# RF_Gen.net
KiCad netlist of a schematic drawn in Altium Designer
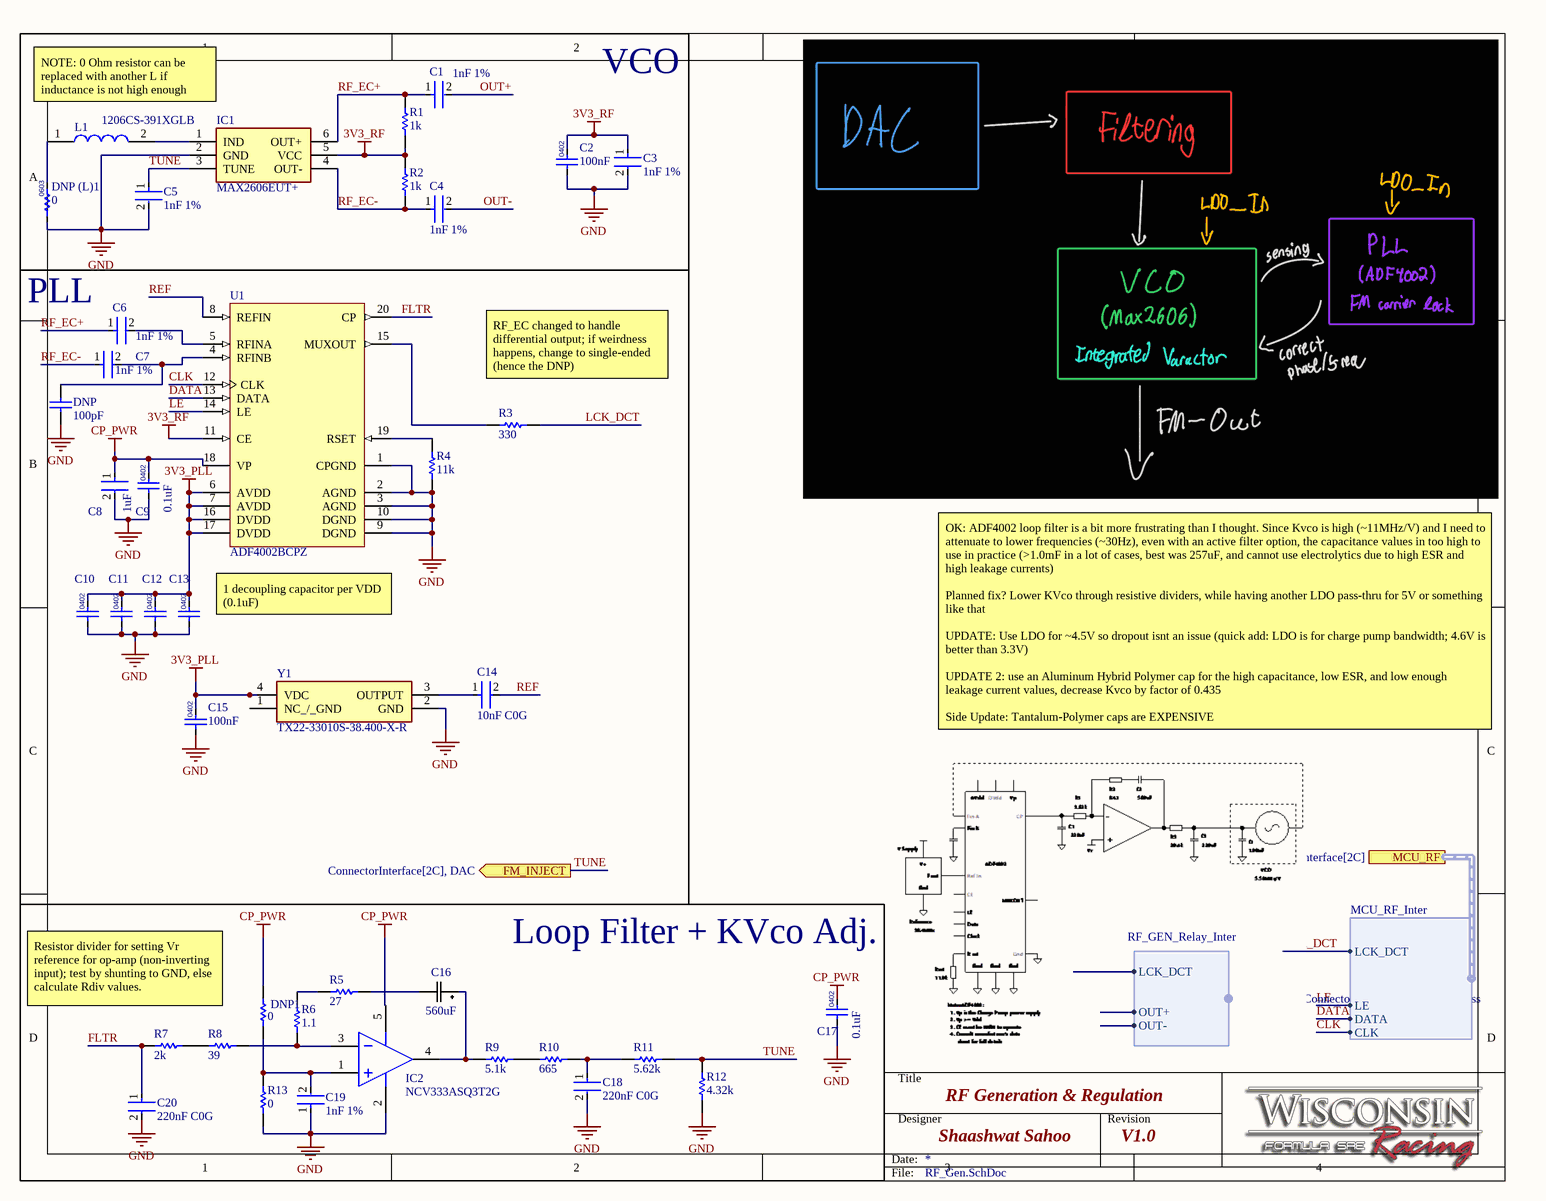
[diagram p0: RF_Gen.SchDoc]

(export (version "E")
  (design (tool "Eeschema 10.0.6"))
  (components
    (comp (ref "C1")
      (value "1nF 1%")
      (footprint "FP-GRT155-0_05-IPC_A")
      (description "Multi-Layer Ceramic Capacitor 1nF 50V C0G ±1% 0402 Paper T/R\r\n\r\nGRT1555C1H102FA02D")
      (libsource (lib "Altium Content Vault") (part "02cd4be3c70576c341d710602a673aa"))
    )
    (comp (ref "C2")
      (value "100nF")
      (footprint "FP-CC0402-IPC_B")
      (fields (field (name "TOLERANCE") "10%"))
      (libsource (lib "University of Wisconsin Formula FSAE") (part "0402 ceramic cap"))
    )
    (comp (ref "C3")
      (value "1nF 1%")
      (footprint "FP-GRT155-0_05-IPC_A")
      (description "Multi-Layer Ceramic Capacitor 1nF 50V C0G ±1% 0402 Paper T/R\r\n\r\nGRT1555C1H102FA02D")
      (libsource (lib "Altium Content Vault") (part "02cd4be3c70576c341d710602a673aa"))
    )
    (comp (ref "C4")
      (value "1nF 1%")
      (footprint "FP-GRT155-0_05-IPC_A")
      (description "Multi-Layer Ceramic Capacitor 1nF 50V C0G ±1% 0402 Paper T/R\r\n\r\nGRT1555C1H102FA02D")
      (libsource (lib "Altium Content Vault") (part "02cd4be3c70576c341d710602a673aa"))
    )
    (comp (ref "C5")
      (value "1nF 1%")
      (footprint "FP-GRT155-0_05-IPC_A")
      (description "Multi-Layer Ceramic Capacitor 1nF 50V C0G ±1% 0402 Paper T/R\r\n\r\nGRT1555C1H102FA02D")
      (libsource (lib "Altium Content Vault") (part "02cd4be3c70576c341d710602a673aa"))
    )
    (comp (ref "C6")
      (value "1nF 1%")
      (footprint "FP-GRT155-0_05-IPC_A")
      (description "Multi-Layer Ceramic Capacitor 1nF 50V C0G ±1% 0402 Paper T/R\r\n\r\nGRT1555C1H102FA02D")
      (libsource (lib "Altium Content Vault") (part "02cd4be3c70576c341d710602a673aa"))
    )
    (comp (ref "C7")
      (value "1nF 1%")
      (footprint "FP-GRT155-0_05-IPC_A")
      (description "Multi-Layer Ceramic Capacitor 1nF 50V C0G ±1% 0402 Paper T/R\r\n\r\nGRT1555C1H102FA02D")
      (libsource (lib "Altium Content Vault") (part "02cd4be3c70576c341d710602a673aa"))
    )
    (comp (ref "C8")
      (value "1uF")
      (footprint "FP-GRM155-0_1-IPC_A")
      (description "Chip Multilayer Ceramic Capacitors for General Purpose, 0402, 1.0uF, X7R, 15%, 10%, 10V")
      (libsource (lib "Altium Content Vault") (part "11868f565c42a9108669ba33697ecf6"))
    )
    (comp (ref "C9")
      (value "0.1uF")
      (footprint "FP-CC0402-IPC_B")
      (fields (field (name "TOLERANCE") "10%"))
      (libsource (lib "University of Wisconsin Formula FSAE") (part "0402 ceramic cap"))
    )
    (comp (ref "C10")
      (value "0.1uF")
      (footprint "FP-CC0402-IPC_B")
      (fields (field (name "TOLERANCE") "10%"))
      (libsource (lib "University of Wisconsin Formula FSAE") (part "0402 ceramic cap"))
    )
    (comp (ref "C11")
      (value "0.1uF")
      (footprint "FP-CC0402-IPC_B")
      (fields (field (name "TOLERANCE") "10%"))
      (libsource (lib "University of Wisconsin Formula FSAE") (part "0402 ceramic cap"))
    )
    (comp (ref "C12")
      (value "0.1uF")
      (footprint "FP-CC0402-IPC_B")
      (fields (field (name "TOLERANCE") "10%"))
      (libsource (lib "University of Wisconsin Formula FSAE") (part "0402 ceramic cap"))
    )
    (comp (ref "C13")
      (value "0.1uF")
      (footprint "FP-CC0402-IPC_B")
      (fields (field (name "TOLERANCE") "10%"))
      (libsource (lib "University of Wisconsin Formula FSAE") (part "0402 ceramic cap"))
    )
    (comp (ref "C14")
      (value "10nF C0G")
      (footprint "FP-GRM155-0_15-MFG")
      (description "Chip Multilayer Ceramic Capacitors for General Purpose, 0402, 10000pF, C0G, 30ppm/°C, 5%, 35V")
      (libsource (lib "Altium Content Vault") (part "b4654b650e69147ec39a6b967a45e02"))
    )
    (comp (ref "C15")
      (value "100nF")
      (footprint "FP-CC0402-IPC_B")
      (fields (field (name "TOLERANCE") "10%"))
      (libsource (lib "University of Wisconsin Formula FSAE") (part "0402 ceramic cap"))
    )
    (comp (ref "C16")
      (value "560uF")
      (footprint "CAP_GY_10X10_NCH")
      (description "Description")
      (fields
        (field (name "MANUFACTURER_PART_NUMBER") "GYB1J560MCQ1GS")
        (field (name "COPYRIGHT") "Copyright (C) 2025 Ultra Librarian. All rights reserved.")
      )
      (libsource (lib "University of Wisconsin Formula FSAE") (part "GYB1J560MCQ1GS"))
    )
    (comp (ref "C17")
      (value "0.1uF")
      (footprint "FP-CC0402-IPC_B")
      (fields (field (name "TOLERANCE") "10%"))
      (libsource (lib "University of Wisconsin Formula FSAE") (part "0402 ceramic cap"))
    )
    (comp (ref "C18")
      (value "220nF C0G")
      (footprint "FP-GRM31C-0_2-e0_3_0_8-IPC_B")
      (description "Chip Multilayer Ceramic Capacitors for General Purpose, 1206, 0.22uF, C0G, 30ppm/°C, 5%, 25V")
      (libsource (lib "Altium Content Vault") (part "02cd4be3c70576c341d710602a673aa"))
    )
    (comp (ref "C19")
      (value "1nF 1%")
      (footprint "FP-GRT155-0_05-IPC_A")
      (description "Multi-Layer Ceramic Capacitor 1nF 50V C0G ±1% 0402 Paper T/R\r\n\r\nGRT1555C1H102FA02D")
      (libsource (lib "Altium Content Vault") (part "02cd4be3c70576c341d710602a673aa"))
    )
    (comp (ref "C20")
      (value "220nF C0G")
      (footprint "FP-GRM31C-0_2-e0_3_0_8-IPC_B")
      (description "Chip Multilayer Ceramic Capacitors for General Purpose, 1206, 0.22uF, C0G, 30ppm/°C, 5%, 25V")
      (libsource (lib "Altium Content Vault") (part "02cd4be3c70576c341d710602a673aa"))
    )
    (comp (ref "DNP")
      (value "100pF")
      (footprint "CAPC1005X55X25ML05T10")
      (fields (field (name "MANUFACTURER") "Murata") (field (name "PART NUMBER") "GRM1555C1H101JA01D"))
      (libsource (lib "Altium Content Vault") (part "CAP"))
    )
    (comp (ref "DNP (L)1")
      (value "0")
      (footprint "Res0603-type-2")
      (description "Fixed Resistor, Metal Glaze/thick Film, 0.1W, 0ohm, Surface Mount, 0603")
      (fields (field (name "TOLERANCE") "0.1%") (field (name "POWER") "100mW"))
      (libsource (lib "University of Wisconsin Formula FSAE") (part "RES 0603"))
    )
    (comp (ref "DNP1")
      (value "0")
      (footprint "RESC1005X40X25NL05T10")
      (fields (field (name "MANUFACTURER") "Yageo / Phycomp") (field (name "PART NUMBER") "RC0402JR-070RL"))
      (libsource (lib "Altium Content Vault") (part "RES"))
    )
    (comp (ref "IC1")
      (value "MAX2606EUT+")
      (footprint "SamacSys:SOT95P280X145-6N")
      (description "Integrated Circuit")
      (fields (field (name "MOUSER PART NUMBER") "700-MAX2606EUT+"))
      (libsource (lib "*") (part "MAX2606EUT+"))
    )
    (comp (ref "IC2")
      (value "NCV333ASQ3T2G")
      (footprint "SOT65P210X110-5N")
      (description "Low Offset Voltage: 10 V max (NCS333)")
      (fields (field (name "MOUSER PART NUMBER") "863-NCV333ASQ3T2G"))
      (libsource (lib "University of Wisconsin Formula FSAE") (part "NCV333ASQ3T2G"))
    )
    (comp (ref "L1")
      (value "1206CS-391XGLB")
      (footprint "SamacSys:INDC3622X152N")
      (description "Inductor")
      (libsource (lib "*") (part "1206CS-391XGLB"))
    )
    (comp (ref "R1")
      (value "1k")
      (footprint "RESC1005X40X25LL05T10")
      (fields (field (name "PART NUMBER") "RC0402JR-071KL") (field (name "MANUFACTURER") "Yageo / Phycomp"))
      (libsource (lib "Altium Content Vault") (part "RES"))
    )
    (comp (ref "R2")
      (value "1k")
      (footprint "RESC1005X40X25LL05T10")
      (fields (field (name "PART NUMBER") "RC0402JR-071KL") (field (name "MANUFACTURER") "Yageo / Phycomp"))
      (libsource (lib "Altium Content Vault") (part "RES"))
    )
    (comp (ref "R3")
      (value "330")
      (footprint "RESC1005X40X25LL05T10")
      (fields (field (name "PART NUMBER") "RC0402FR-07330RL") (field (name "MANUFACTURER") "Yageo / Phycomp"))
      (libsource (lib "Altium Content Vault") (part "RES"))
    )
    (comp (ref "R4")
      (value "11k")
      (footprint "RESC1005X40X25NL05T10")
      (fields (field (name "PART NUMBER") "RC0402FR-075K1L") (field (name "MANUFACTURER") "Yageo / Phycomp"))
      (libsource (lib "Altium Content Vault") (part "RES"))
    )
    (comp (ref "R5")
      (value "27")
      (footprint "RESC1005X40X25LL05T10")
      (fields (field (name "PART NUMBER") "RC0402FR-0727RL") (field (name "MANUFACTURER") "Yageo / Phycomp"))
      (libsource (lib "Altium Content Vault") (part "RES"))
    )
    (comp (ref "R6")
      (value "1.1")
      (footprint "RESC1005X40X25NL05T10")
      (fields (field (name "PART NUMBER") "RC0402FR-071R1L") (field (name "MANUFACTURER") "Yageo / Phycomp"))
      (libsource (lib "Altium Content Vault") (part "RES"))
    )
    (comp (ref "R7")
      (value "2k")
      (footprint "RESC1005X35X25NL10T10")
      (fields (field (name "MANUFACTURER") "Yageo") (field (name "PART NUMBER") "RT0402BRD072KL"))
      (libsource (lib "Altium Content Vault") (part "RES"))
    )
    (comp (ref "R8")
      (value "39")
      (footprint "RESC1005X40X25LL05T10")
      (fields (field (name "MANUFACTURER") "Yageo / Phycomp") (field (name "PART NUMBER") "RC0402FR-0739RL"))
      (libsource (lib "Altium Content Vault") (part "RES"))
    )
    (comp (ref "R9")
      (value "5.1k")
      (footprint "RESC1005X40X25NL05T10")
      (fields (field (name "PART NUMBER") "RC0402FR-075K1L") (field (name "MANUFACTURER") "Yageo / Phycomp"))
      (libsource (lib "Altium Content Vault") (part "RES"))
    )
    (comp (ref "R10")
      (value "665")
      (footprint "RESC1005X40X25ML05T10")
      (fields (field (name "PART NUMBER") "RC0402FR-07665RL") (field (name "MANUFACTURER") "Yageo / Phycomp"))
      (libsource (lib "Altium Content Vault") (part "RES"))
    )
    (comp (ref "R11")
      (value "5.62k")
      (footprint "RESC1005X40X25LL05T10")
      (fields (field (name "PART NUMBER") "RC0402FR-075K62L") (field (name "MANUFACTURER") "Yageo / Phycomp"))
      (libsource (lib "Altium Content Vault") (part "RES"))
    )
    (comp (ref "R12")
      (value "4.32k")
      (footprint "RESC1005X40X25NL05T10")
      (fields (field (name "PART NUMBER") "RC0402FR-074K32L") (field (name "MANUFACTURER") "Yageo / Phycomp"))
      (libsource (lib "Altium Content Vault") (part "RES"))
    )
    (comp (ref "R13")
      (value "0")
      (footprint "RESC1005X40X25NL05T10")
      (fields (field (name "MANUFACTURER") "Yageo / Phycomp") (field (name "PART NUMBER") "RC0402JR-070RL"))
      (libsource (lib "Altium Content Vault") (part "RES"))
    )
    (comp (ref "U1")
      (value "ADF4002BCPZ")
      (footprint "ADI-CP-20-1_L")
      (description "Clock Generator/Frequency Synthesizer /PLL")
      (libsource (lib "University of Wisconsin Formula FSAE") (part "ADI-ADF4002-CP-20-1"))
    )
    (comp (ref "Y1")
      (value "TX22-33010S-38.400-X-R")
      (footprint "SamacSys:TX2233010S38400XR")
      (description "Crystal or Oscillator")
      (libsource (lib "*") (part "TX22-33010S-38.400-X-R"))
    )
  )
  (nets
    (net (code "3") (name "/CLK") (class "Default")
      (node (ref "U1") (pin "12") (pinfunction "CLK_12") (pintype "input"))
    )
    (net (code "4") (name "/DATA") (class "Default")
      (node (ref "U1") (pin "13") (pinfunction "DATA_13") (pintype "input"))
    )
    (net (code "5") (name "/FLTR") (class "Default")
      (node (ref "C20") (pin "1") (pinfunction "1_1") (pintype "passive"))
      (node (ref "R7") (pin "1") (pinfunction "1_1") (pintype "passive"))
      (node (ref "U1") (pin "20") (pinfunction "CP_20") (pintype "output"))
    )
    (net (code "6") (name "/LCK_DCT") (class "Default")
      (node (ref "R3") (pin "2") (pinfunction "2_2") (pintype "passive"))
    )
    (net (code "7") (name "/LE") (class "Default")
      (node (ref "U1") (pin "14") (pinfunction "LE_14") (pintype "input"))
    )
    (net (code "8") (name "/OUT+") (class "Default")
      (node (ref "C1") (pin "2") (pinfunction "2_2") (pintype "passive"))
    )
    (net (code "9") (name "/OUT-") (class "Default")
      (node (ref "C4") (pin "2") (pinfunction "2_2") (pintype "passive"))
    )
    (net (code "10") (name "/REF") (class "Default")
      (node (ref "C14") (pin "2") (pinfunction "2_2") (pintype "passive"))
      (node (ref "U1") (pin "8") (pinfunction "REFIN_8") (pintype "input"))
    )
    (net (code "11") (name "/RF_EC+") (class "Default")
      (node (ref "C1") (pin "1") (pinfunction "1_1") (pintype "passive"))
      (node (ref "C6") (pin "1") (pinfunction "1_1") (pintype "passive"))
      (node (ref "IC1") (pin "6") (pinfunction "OUT+_6") (pintype "passive"))
      (node (ref "R1") (pin "2") (pinfunction "2_2") (pintype "passive"))
    )
    (net (code "12") (name "/RF_EC-") (class "Default")
      (node (ref "C4") (pin "1") (pinfunction "1_1") (pintype "passive"))
      (node (ref "C7") (pin "1") (pinfunction "1_1") (pintype "passive"))
      (node (ref "IC1") (pin "4") (pinfunction "OUT-_4") (pintype "passive"))
      (node (ref "R2") (pin "1") (pinfunction "1_1") (pintype "passive"))
    )
    (net (code "13") (name "/TUNE") (class "Default")
      (node (ref "C5") (pin "1") (pinfunction "1_1") (pintype "passive"))
      (node (ref "IC1") (pin "3") (pinfunction "TUNE_3") (pintype "passive"))
      (node (ref "R11") (pin "2") (pinfunction "2_2") (pintype "passive"))
      (node (ref "R12") (pin "2") (pinfunction "2_2") (pintype "passive"))
    )
    (net (code "16") (name "3V3_PLL") (class "Default")
      (node (ref "C10") (pin "2") (pinfunction "2_2") (pintype "passive"))
      (node (ref "C11") (pin "2") (pinfunction "2_2") (pintype "passive"))
      (node (ref "C12") (pin "2") (pinfunction "2_2") (pintype "passive"))
      (node (ref "C13") (pin "2") (pinfunction "2_2") (pintype "passive"))
      (node (ref "C15") (pin "2") (pinfunction "2_2") (pintype "passive"))
      (node (ref "U1") (pin "16") (pinfunction "DVDD_16") (pintype "power_in"))
      (node (ref "U1") (pin "17") (pinfunction "DVDD_17") (pintype "power_in"))
      (node (ref "U1") (pin "6") (pinfunction "AVDD_6") (pintype "power_in"))
      (node (ref "U1") (pin "7") (pinfunction "AVDD_7") (pintype "power_in"))
      (node (ref "Y1") (pin "4") (pinfunction "VDC_4") (pintype "passive"))
    )
    (net (code "17") (name "3V3_RF") (class "Default")
      (node (ref "C2") (pin "2") (pinfunction "2_2") (pintype "passive"))
      (node (ref "C3") (pin "1") (pinfunction "1_1") (pintype "passive"))
      (node (ref "IC1") (pin "5") (pinfunction "VCC_5") (pintype "passive"))
      (node (ref "R1") (pin "1") (pinfunction "1_1") (pintype "passive"))
      (node (ref "R2") (pin "2") (pinfunction "2_2") (pintype "passive"))
      (node (ref "U1") (pin "11") (pinfunction "CE_11") (pintype "input"))
    )
    (net (code "18") (name "CP_PWR") (class "Default")
      (node (ref "C17") (pin "2") (pinfunction "2_2") (pintype "passive"))
      (node (ref "C8") (pin "1") (pinfunction "1_1") (pintype "passive"))
      (node (ref "C9") (pin "2") (pinfunction "2_2") (pintype "passive"))
      (node (ref "DNP1") (pin "2") (pinfunction "2_2") (pintype "passive"))
      (node (ref "IC2") (pin "5") (pinfunction "V-_5") (pintype "power_in"))
      (node (ref "U1") (pin "18") (pinfunction "VP_18") (pintype "power_in"))
    )
    (net (code "19") (name "GND") (class "Default")
      (node (ref "C10") (pin "1") (pinfunction "1_1") (pintype "passive"))
      (node (ref "C11") (pin "1") (pinfunction "1_1") (pintype "passive"))
      (node (ref "C12") (pin "1") (pinfunction "1_1") (pintype "passive"))
      (node (ref "C13") (pin "1") (pinfunction "1_1") (pintype "passive"))
      (node (ref "C15") (pin "1") (pinfunction "1_1") (pintype "passive"))
      (node (ref "C17") (pin "1") (pinfunction "1_1") (pintype "passive"))
      (node (ref "C18") (pin "2") (pinfunction "2_2") (pintype "passive"))
      (node (ref "C19") (pin "1") (pinfunction "1_1") (pintype "passive"))
      (node (ref "C2") (pin "1") (pinfunction "1_1") (pintype "passive"))
      (node (ref "C20") (pin "2") (pinfunction "2_2") (pintype "passive"))
      (node (ref "C3") (pin "2") (pinfunction "2_2") (pintype "passive"))
      (node (ref "C5") (pin "2") (pinfunction "2_2") (pintype "passive"))
      (node (ref "C8") (pin "2") (pinfunction "2_2") (pintype "passive"))
      (node (ref "C9") (pin "1") (pinfunction "1_1") (pintype "passive"))
      (node (ref "DNP") (pin "2") (pinfunction "2_2") (pintype "passive"))
      (node (ref "DNP (L)1") (pin "1") (pinfunction "1_1") (pintype "passive"))
      (node (ref "IC1") (pin "2") (pinfunction "GND_2") (pintype "passive"))
      (node (ref "IC2") (pin "2") (pinfunction "V-_2") (pintype "power_in"))
      (node (ref "R12") (pin "1") (pinfunction "1_1") (pintype "passive"))
      (node (ref "R13") (pin "1") (pinfunction "1_1") (pintype "passive"))
      (node (ref "R4") (pin "1") (pinfunction "1_1") (pintype "passive"))
      (node (ref "U1") (pin "1") (pinfunction "CPGND_1") (pintype "power_in"))
      (node (ref "U1") (pin "10") (pinfunction "DGND_10") (pintype "power_in"))
      (node (ref "U1") (pin "2") (pinfunction "AGND_2") (pintype "power_in"))
      (node (ref "U1") (pin "3") (pinfunction "AGND_3") (pintype "power_in"))
      (node (ref "U1") (pin "9") (pinfunction "DGND_9") (pintype "power_in"))
      (node (ref "Y1") (pin "2") (pinfunction "GND_2") (pintype "passive"))
    )
    (net (code "20") (name "Net-(C16-Pad2)") (class "Default")
      (node (ref "C16") (pin "2") (pinfunction "2_2") (pintype "passive"))
      (node (ref "R5") (pin "2") (pinfunction "2_2") (pintype "passive"))
    )
    (net (code "21") (name "Net-(C18-Pad1)") (class "Default")
      (node (ref "C18") (pin "1") (pinfunction "1_1") (pintype "passive"))
      (node (ref "R10") (pin "2") (pinfunction "2_2") (pintype "passive"))
      (node (ref "R11") (pin "1") (pinfunction "1_1") (pintype "passive"))
    )
    (net (code "22") (name "Net-(DNP (L)1-Pad2)") (class "Default")
      (node (ref "DNP (L)1") (pin "2") (pinfunction "2_2") (pintype "passive"))
      (node (ref "L1") (pin "1") (pinfunction "1_1") (pintype "passive"))
    )
    (net (code "23") (name "Net-(IC1-IND)") (class "Default")
      (node (ref "IC1") (pin "1") (pinfunction "IND_1") (pintype "passive"))
      (node (ref "L1") (pin "2") (pinfunction "2_2") (pintype "passive"))
    )
    (net (code "24") (name "Net-(IC2-IN+)") (class "Default")
      (node (ref "C19") (pin "2") (pinfunction "2_2") (pintype "passive"))
      (node (ref "DNP1") (pin "1") (pinfunction "1_1") (pintype "passive"))
      (node (ref "IC2") (pin "1") (pinfunction "IN+_1") (pintype "passive"))
      (node (ref "R13") (pin "2") (pinfunction "2_2") (pintype "passive"))
    )
    (net (code "25") (name "Net-(IC2-IN-)") (class "Default")
      (node (ref "IC2") (pin "3") (pinfunction "IN-_3") (pintype "passive"))
      (node (ref "R6") (pin "1") (pinfunction "1_1") (pintype "passive"))
      (node (ref "R8") (pin "2") (pinfunction "2_2") (pintype "passive"))
    )
    (net (code "26") (name "Net-(IC2-OUT)") (class "Default")
      (node (ref "C16") (pin "1") (pinfunction "1_1") (pintype "passive"))
      (node (ref "IC2") (pin "4") (pinfunction "OUT_4") (pintype "passive"))
      (node (ref "R9") (pin "1") (pinfunction "1_1") (pintype "passive"))
    )
    (net (code "27") (name "Net-(R5-Pad1)") (class "Default")
      (node (ref "R5") (pin "1") (pinfunction "1_1") (pintype "passive"))
      (node (ref "R6") (pin "2") (pinfunction "2_2") (pintype "passive"))
    )
    (net (code "28") (name "Net-(R7-Pad2)") (class "Default")
      (node (ref "R7") (pin "2") (pinfunction "2_2") (pintype "passive"))
      (node (ref "R8") (pin "1") (pinfunction "1_1") (pintype "passive"))
    )
    (net (code "29") (name "Net-(R10-Pad1)") (class "Default")
      (node (ref "R10") (pin "1") (pinfunction "1_1") (pintype "passive"))
      (node (ref "R9") (pin "2") (pinfunction "2_2") (pintype "passive"))
    )
    (net (code "30") (name "Net-(U1-MUXOUT)") (class "Default")
      (node (ref "R3") (pin "1") (pinfunction "1_1") (pintype "passive"))
      (node (ref "U1") (pin "15") (pinfunction "MUXOUT_15") (pintype "output"))
    )
    (net (code "31") (name "Net-(U1-RFINA)") (class "Default")
      (node (ref "C6") (pin "2") (pinfunction "2_2") (pintype "passive"))
      (node (ref "U1") (pin "5") (pinfunction "RFINA_5") (pintype "input"))
    )
    (net (code "32") (name "Net-(U1-RFINB)") (class "Default")
      (node (ref "C7") (pin "2") (pinfunction "2_2") (pintype "passive"))
      (node (ref "DNP") (pin "1") (pinfunction "1_1") (pintype "passive"))
      (node (ref "U1") (pin "4") (pinfunction "RFINB_4") (pintype "input"))
    )
    (net (code "33") (name "Net-(U1-RSET)") (class "Default")
      (node (ref "R4") (pin "2") (pinfunction "2_2") (pintype "passive"))
      (node (ref "U1") (pin "19") (pinfunction "RSET_19") (pintype "input"))
    )
    (net (code "34") (name "Net-(Y1-OUTPUT)") (class "Default")
      (node (ref "C14") (pin "1") (pinfunction "1_1") (pintype "passive"))
      (node (ref "Y1") (pin "3") (pinfunction "OUTPUT_3") (pintype "passive"))
    )
    (net (code "35") (name "unconnected-(Y1-NC_{slash}_GND-Pad1)") (class "Default")
      (node (ref "Y1") (pin "1") (pinfunction "NC_/_GND_1") (pintype "passive"))
    )
  )
)
